# tinyduino-breakout-mk-1_0.net
KiCad netlist of a schematic drawn in EAGLE
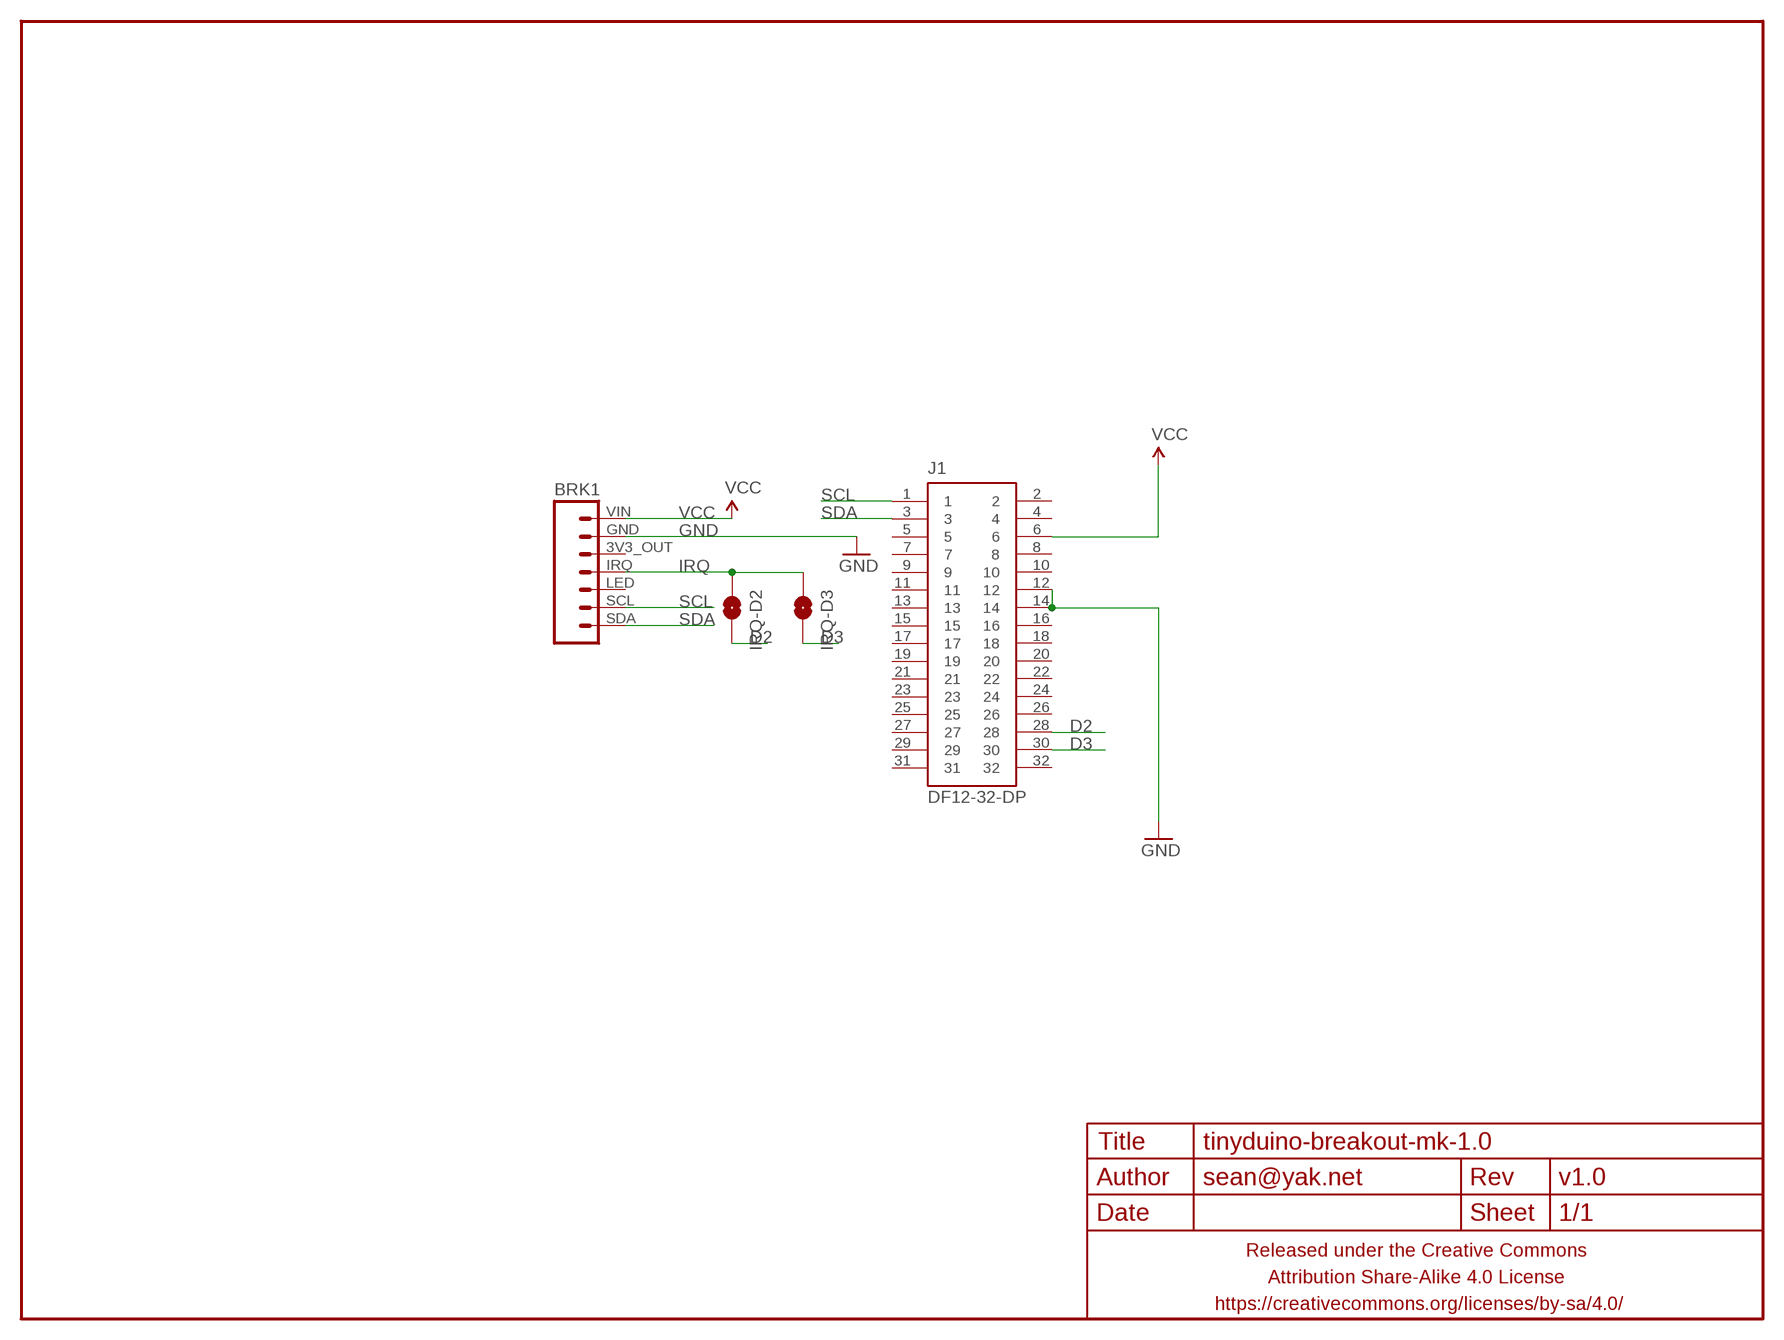
[diagram p0: schematic, sheet 1]

(export (version "E")
  (design (tool "Eeschema 10.0.6"))
  (components
    (comp (ref "BRK1")
      (value "ADAFRUIT-SI1145-BREAKOUT")
      (footprint "eagle-import:ADAFRUIT-SI1145-BREAKOUT")
      (libsource (lib "eagle-import") (part "ADAFRUIT-SI1145-BREAKOUT"))
    )
    (comp (ref "FRAME1")
      (value "FRAME-LETTERNO_PACKAGE")
      (footprint "eagle-import:DUMMY")
      (fields (field (name "DESIGNER") "sean@yak.net") (field (name "VERSION") "v1.0"))
      (libsource (lib "eagle-import") (part "FRAME-LETTERNO_PACKAGE"))
    )
    (comp (ref "IRQ-D2")
      (value "JUMPER-PAD-2-NOYES_SILK")
      (footprint "eagle-import:PAD-JUMPER-2-NO_YES_SILK")
      (libsource (lib "eagle-import") (part "JUMPER-PAD-2-NOYES_SILK"))
    )
    (comp (ref "IRQ-D3")
      (value "JUMPER-PAD-2-NOYES_SILK")
      (footprint "eagle-import:PAD-JUMPER-2-NO_YES_SILK")
      (libsource (lib "eagle-import") (part "JUMPER-PAD-2-NOYES_SILK"))
    )
    (comp (ref "J1")
      (value "DF12-32-DP")
      (footprint "eagle-import:DF12-32-DP")
      (fields (field (name "PARTNO") "AS-ITM-00015"))
      (libsource (lib "eagle-import") (part "AS-ITM-00015"))
    )
  )
  (nets
    (net (code "1") (name "/D2") (class "Default")
      (node (ref "IRQ-D2") (pin "2") (pinfunction "2_2") (pintype "passive"))
      (node (ref "J1") (pin "28") (pinfunction "28_28") (pintype "bidirectional"))
    )
    (net (code "2") (name "/D3") (class "Default")
      (node (ref "IRQ-D3") (pin "2") (pinfunction "2_2") (pintype "passive"))
      (node (ref "J1") (pin "30") (pinfunction "30_30") (pintype "bidirectional"))
    )
    (net (code "3") (name "/IRQ") (class "Default")
      (node (ref "BRK1") (pin "IRQ") (pinfunction "IRQ_IRQ") (pintype "passive"))
      (node (ref "IRQ-D2") (pin "1") (pinfunction "1_1") (pintype "passive"))
      (node (ref "IRQ-D3") (pin "1") (pinfunction "1_1") (pintype "passive"))
    )
    (net (code "4") (name "/SCL") (class "Default")
      (node (ref "BRK1") (pin "SCL") (pinfunction "SCL_SCL") (pintype "passive"))
      (node (ref "J1") (pin "1") (pinfunction "1_1") (pintype "bidirectional"))
    )
    (net (code "5") (name "/SDA") (class "Default")
      (node (ref "BRK1") (pin "SDA") (pinfunction "SDA_SDA") (pintype "passive"))
      (node (ref "J1") (pin "3") (pinfunction "3_3") (pintype "bidirectional"))
    )
    (net (code "6") (name "GND") (class "Default")
      (node (ref "BRK1") (pin "GND") (pinfunction "GND_GND") (pintype "passive"))
      (node (ref "J1") (pin "12") (pinfunction "12_12") (pintype "bidirectional"))
      (node (ref "J1") (pin "14") (pinfunction "14_14") (pintype "bidirectional"))
    )
    (net (code "7") (name "VCC") (class "Default")
      (node (ref "BRK1") (pin "VIN") (pinfunction "VIN_VIN") (pintype "passive"))
      (node (ref "J1") (pin "6") (pinfunction "6_6") (pintype "bidirectional"))
    )
    (net (code "8") (name "unconnected-(BRK1-Pad3V3_OUT)") (class "Default")
      (node (ref "BRK1") (pin "3V3_OUT") (pinfunction "3V3_OUT_3V3_OUT") (pintype "passive"))
    )
    (net (code "9") (name "unconnected-(BRK1-PadLED)") (class "Default")
      (node (ref "BRK1") (pin "LED") (pinfunction "LED_LED") (pintype "passive"))
    )
    (net (code "10") (name "unconnected-(J1-Pad2)") (class "Default")
      (node (ref "J1") (pin "2") (pinfunction "2_2") (pintype "bidirectional"))
    )
    (net (code "11") (name "unconnected-(J1-Pad4)") (class "Default")
      (node (ref "J1") (pin "4") (pinfunction "4_4") (pintype "bidirectional"))
    )
    (net (code "12") (name "unconnected-(J1-Pad5)") (class "Default")
      (node (ref "J1") (pin "5") (pinfunction "5_5") (pintype "bidirectional"))
    )
    (net (code "13") (name "unconnected-(J1-Pad7)") (class "Default")
      (node (ref "J1") (pin "7") (pinfunction "7_7") (pintype "bidirectional"))
    )
    (net (code "14") (name "unconnected-(J1-Pad8)") (class "Default")
      (node (ref "J1") (pin "8") (pinfunction "8_8") (pintype "bidirectional"))
    )
    (net (code "15") (name "unconnected-(J1-Pad9)") (class "Default")
      (node (ref "J1") (pin "9") (pinfunction "9_9") (pintype "bidirectional"))
    )
    (net (code "16") (name "unconnected-(J1-Pad10)") (class "Default")
      (node (ref "J1") (pin "10") (pinfunction "10_10") (pintype "bidirectional"))
    )
    (net (code "17") (name "unconnected-(J1-Pad11)") (class "Default")
      (node (ref "J1") (pin "11") (pinfunction "11_11") (pintype "bidirectional"))
    )
    (net (code "18") (name "unconnected-(J1-Pad13)") (class "Default")
      (node (ref "J1") (pin "13") (pinfunction "13_13") (pintype "bidirectional"))
    )
    (net (code "19") (name "unconnected-(J1-Pad15)") (class "Default")
      (node (ref "J1") (pin "15") (pinfunction "15_15") (pintype "bidirectional"))
    )
    (net (code "20") (name "unconnected-(J1-Pad16)") (class "Default")
      (node (ref "J1") (pin "16") (pinfunction "16_16") (pintype "bidirectional"))
    )
    (net (code "21") (name "unconnected-(J1-Pad17)") (class "Default")
      (node (ref "J1") (pin "17") (pinfunction "17_17") (pintype "bidirectional"))
    )
    (net (code "22") (name "unconnected-(J1-Pad18)") (class "Default")
      (node (ref "J1") (pin "18") (pinfunction "18_18") (pintype "bidirectional"))
    )
    (net (code "23") (name "unconnected-(J1-Pad19)") (class "Default")
      (node (ref "J1") (pin "19") (pinfunction "19_19") (pintype "bidirectional"))
    )
    (net (code "24") (name "unconnected-(J1-Pad20)") (class "Default")
      (node (ref "J1") (pin "20") (pinfunction "20_20") (pintype "bidirectional"))
    )
    (net (code "25") (name "unconnected-(J1-Pad21)") (class "Default")
      (node (ref "J1") (pin "21") (pinfunction "21_21") (pintype "bidirectional"))
    )
    (net (code "26") (name "unconnected-(J1-Pad22)") (class "Default")
      (node (ref "J1") (pin "22") (pinfunction "22_22") (pintype "bidirectional"))
    )
    (net (code "27") (name "unconnected-(J1-Pad23)") (class "Default")
      (node (ref "J1") (pin "23") (pinfunction "23_23") (pintype "bidirectional"))
    )
    (net (code "28") (name "unconnected-(J1-Pad24)") (class "Default")
      (node (ref "J1") (pin "24") (pinfunction "24_24") (pintype "bidirectional"))
    )
    (net (code "29") (name "unconnected-(J1-Pad25)") (class "Default")
      (node (ref "J1") (pin "25") (pinfunction "25_25") (pintype "bidirectional"))
    )
    (net (code "30") (name "unconnected-(J1-Pad26)") (class "Default")
      (node (ref "J1") (pin "26") (pinfunction "26_26") (pintype "bidirectional"))
    )
    (net (code "31") (name "unconnected-(J1-Pad27)") (class "Default")
      (node (ref "J1") (pin "27") (pinfunction "27_27") (pintype "bidirectional"))
    )
    (net (code "32") (name "unconnected-(J1-Pad29)") (class "Default")
      (node (ref "J1") (pin "29") (pinfunction "29_29") (pintype "bidirectional"))
    )
    (net (code "33") (name "unconnected-(J1-Pad31)") (class "Default")
      (node (ref "J1") (pin "31") (pinfunction "31_31") (pintype "bidirectional"))
    )
    (net (code "34") (name "unconnected-(J1-Pad32)") (class "Default")
      (node (ref "J1") (pin "32") (pinfunction "32_32") (pintype "bidirectional"))
    )
  )
)
